# honeywell-mpr-breakout.net
KiCad netlist of a schematic drawn in EAGLE
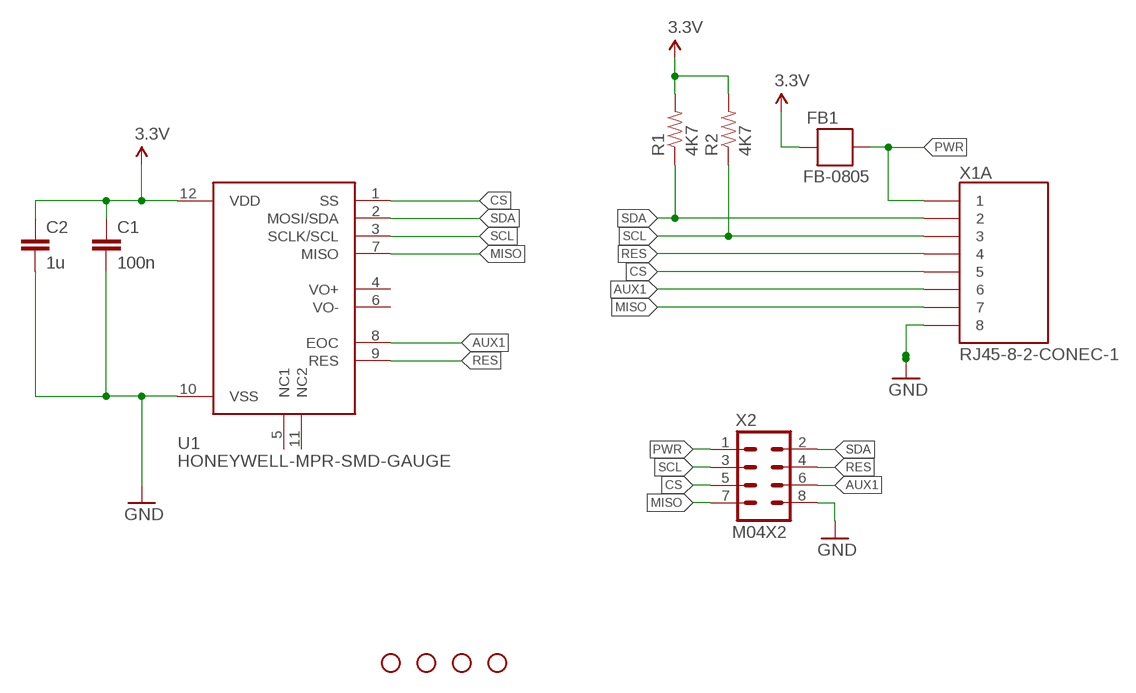
[diagram p0: schematic, sheet 1]

(export (version "E")
  (design (tool "Eeschema 10.0.6"))
  (components
    (comp (ref "C1")
      (value "100n")
      (footprint "eagle-import:0805")
      (libsource (lib "eagle-import") (part "CAP0805"))
    )
    (comp (ref "C2")
      (value "1u")
      (footprint "eagle-import:0805")
      (libsource (lib "eagle-import") (part "CAP0805"))
    )
    (comp (ref "FB1")
      (value "FB-0805")
      (footprint "eagle-import:0805")
      (libsource (lib "eagle-import") (part "FB-0805"))
    )
    (comp (ref "JP1")
      (value "STAND-OFF")
      (footprint "eagle-import:STAND-OFF")
      (libsource (lib "eagle-import") (part "STAND-OFF"))
    )
    (comp (ref "JP2")
      (value "STAND-OFF")
      (footprint "eagle-import:STAND-OFF")
      (libsource (lib "eagle-import") (part "STAND-OFF"))
    )
    (comp (ref "JP3")
      (value "STAND-OFF")
      (footprint "eagle-import:STAND-OFF")
      (libsource (lib "eagle-import") (part "STAND-OFF"))
    )
    (comp (ref "JP4")
      (value "STAND-OFF")
      (footprint "eagle-import:STAND-OFF")
      (libsource (lib "eagle-import") (part "STAND-OFF"))
    )
    (comp (ref "R1")
      (value "4K7")
      (footprint "eagle-import:0805")
      (libsource (lib "eagle-import") (part "RESISTOR0805-RES"))
    )
    (comp (ref "R2")
      (value "4K7")
      (footprint "eagle-import:0805")
      (libsource (lib "eagle-import") (part "RESISTOR0805-RES"))
    )
    (comp (ref "U1")
      (value "HONEYWELL-MPR-SMD-GAUGE")
      (footprint "eagle-import:HONEYWELL-MPR-GAUGE")
      (libsource (lib "eagle-import") (part "HONEYWELL-MPR-SMD-GAUGE"))
    )
    (comp (ref "X1")
      (value "RJ45-8-2-CONEC-1")
      (footprint "eagle-import:CONEC-33TS3004ST-88001")
      (libsource (lib "eagle-import") (part "RJ45-8-2-CONEC-1"))
    )
    (comp (ref "X2")
      (value "M04X2")
      (footprint "eagle-import:2X4")
      (libsource (lib "eagle-import") (part "M04X2"))
    )
  )
  (nets
    (net (code "1") (name "3.3V") (class "Default")
      (node (ref "C1") (pin "1") (pinfunction "1_1") (pintype "passive"))
      (node (ref "C2") (pin "1") (pinfunction "1_1") (pintype "passive"))
      (node (ref "FB1") (pin "2") (pinfunction "P$2_2") (pintype "bidirectional"))
      (node (ref "R1") (pin "2") (pinfunction "2_2") (pintype "passive"))
      (node (ref "R2") (pin "2") (pinfunction "2_2") (pintype "passive"))
      (node (ref "U1") (pin "12") (pinfunction "VDD_12") (pintype "input"))
    )
    (net (code "2") (name "AUX1") (class "Default")
      (node (ref "U1") (pin "8") (pinfunction "EOC_8") (pintype "bidirectional"))
      (node (ref "X1") (pin "6") (pinfunction "6_6") (pintype "bidirectional"))
      (node (ref "X2") (pin "6") (pinfunction "6_6") (pintype "passive"))
    )
    (net (code "3") (name "CS") (class "Default")
      (node (ref "U1") (pin "1") (pinfunction "SS_1") (pintype "bidirectional"))
      (node (ref "X1") (pin "5") (pinfunction "5_5") (pintype "bidirectional"))
      (node (ref "X2") (pin "5") (pinfunction "5_5") (pintype "passive"))
    )
    (net (code "4") (name "GND") (class "Default")
      (node (ref "C1") (pin "2") (pinfunction "2_2") (pintype "passive"))
      (node (ref "C2") (pin "2") (pinfunction "2_2") (pintype "passive"))
      (node (ref "U1") (pin "10") (pinfunction "VSS_10") (pintype "input"))
      (node (ref "X1") (pin "8") (pinfunction "8_8") (pintype "bidirectional"))
      (node (ref "X1") (pin "M1") (pinfunction "P$1_M1") (pintype "bidirectional"))
      (node (ref "X1") (pin "M2") (pinfunction "P$1_M2") (pintype "bidirectional"))
      (node (ref "X2") (pin "8") (pinfunction "8_8") (pintype "passive"))
    )
    (net (code "5") (name "MISO") (class "Default")
      (node (ref "U1") (pin "7") (pinfunction "MISO_7") (pintype "bidirectional"))
      (node (ref "X1") (pin "7") (pinfunction "7_7") (pintype "bidirectional"))
      (node (ref "X2") (pin "7") (pinfunction "7_7") (pintype "passive"))
    )
    (net (code "6") (name "PWR") (class "Default")
      (node (ref "FB1") (pin "1") (pinfunction "P$1_1") (pintype "bidirectional"))
      (node (ref "X1") (pin "1") (pinfunction "1_1") (pintype "bidirectional"))
      (node (ref "X2") (pin "1") (pinfunction "1_1") (pintype "passive"))
    )
    (net (code "7") (name "RES") (class "Default")
      (node (ref "U1") (pin "9") (pinfunction "RES_9") (pintype "bidirectional"))
      (node (ref "X1") (pin "4") (pinfunction "4_4") (pintype "bidirectional"))
      (node (ref "X2") (pin "4") (pinfunction "4_4") (pintype "passive"))
    )
    (net (code "8") (name "SCL") (class "Default")
      (node (ref "R2") (pin "1") (pinfunction "1_1") (pintype "passive"))
      (node (ref "U1") (pin "3") (pinfunction "SCLK/SCL_3") (pintype "bidirectional"))
      (node (ref "X1") (pin "3") (pinfunction "3_3") (pintype "bidirectional"))
      (node (ref "X2") (pin "3") (pinfunction "3_3") (pintype "passive"))
    )
    (net (code "9") (name "SDA") (class "Default")
      (node (ref "R1") (pin "1") (pinfunction "1_1") (pintype "passive"))
      (node (ref "U1") (pin "2") (pinfunction "MOSI/SDA_2") (pintype "bidirectional"))
      (node (ref "X1") (pin "2") (pinfunction "2_2") (pintype "bidirectional"))
      (node (ref "X2") (pin "2") (pinfunction "2_2") (pintype "passive"))
    )
    (net (code "10") (name "unconnected-(U1-NC1-Pad5)") (class "Default")
      (node (ref "U1") (pin "5") (pinfunction "NC1_5") (pintype "no_connect"))
    )
    (net (code "11") (name "unconnected-(U1-NC2-Pad11)") (class "Default")
      (node (ref "U1") (pin "11") (pinfunction "NC2_11") (pintype "no_connect"))
    )
    (net (code "12") (name "unconnected-(U1-VO+-Pad4)") (class "Default")
      (node (ref "U1") (pin "4") (pinfunction "VO+_4") (pintype "bidirectional"))
    )
    (net (code "13") (name "unconnected-(U1-VO--Pad6)") (class "Default")
      (node (ref "U1") (pin "6") (pinfunction "VO-_6") (pintype "bidirectional"))
    )
  )
)
